# raspi-rfid-rc522.net
KiCad netlist of a schematic drawn in EAGLE
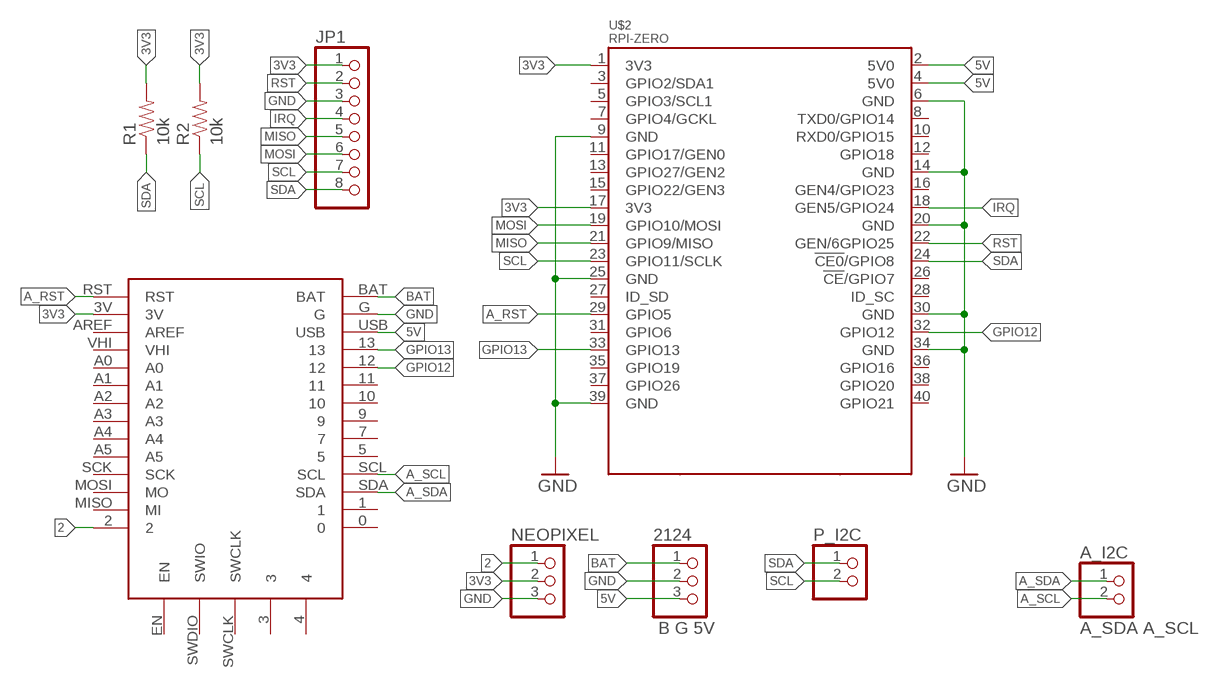
[diagram p0: schematic, sheet 1]

(export (version "E")
  (design (tool "Eeschema 10.0.6"))
  (components
    (comp (ref "2124")
      (value "B G 5V")
      (footprint "eagle-import:1X03")
      (libsource (lib "eagle-import") (part "PINHD-1X3"))
    )
    (comp (ref "A_I2C")
      (value "A_SDA A_SCL")
      (footprint "eagle-import:1X02")
      (libsource (lib "eagle-import") (part "PINHD-1X2"))
    )
    (comp (ref "JP1")
      (value "PINHD-1X8/90")
      (footprint "eagle-import:1X08_90")
      (libsource (lib "eagle-import") (part "PINHD-1X8/90"))
    )
    (comp (ref "NEOPIXEL")
      (value "PINHD-1X3")
      (footprint "eagle-import:1X03")
      (libsource (lib "eagle-import") (part "PINHD-1X3"))
    )
    (comp (ref "P_I2C")
      (value "PINHD-1X2")
      (footprint "eagle-import:1X02")
      (libsource (lib "eagle-import") (part "PINHD-1X2"))
    )
    (comp (ref "R1")
      (value "10k")
      (footprint "eagle-import:0603-RES")
      (libsource (lib "eagle-import") (part "RESISTOR0603-RES"))
    )
    (comp (ref "R2")
      (value "10k")
      (footprint "eagle-import:0603-RES")
      (libsource (lib "eagle-import") (part "RESISTOR0603-RES"))
    )
    (comp (ref "U$1")
      (value "ITSYBITSYM4")
      (footprint "eagle-import:ITSYBITSYM4")
      (libsource (lib "eagle-import") (part "ITSYBITSYM4"))
    )
    (comp (ref "U$2")
      (value "RPI-ZERO")
      (footprint "eagle-import:RASPBERRYPI_BASTELSTUBE_V13_RASPI_BOARD_B+_FULL")
      (libsource (lib "eagle-import") (part "RPI-ZERO"))
    )
  )
  (nets
    (net (code "1") (name "2") (class "Default")
      (node (ref "NEOPIXEL") (pin "1") (pinfunction "1_1") (pintype "passive"))
      (node (ref "U$1") (pin "2") (pinfunction "2_2") (pintype "bidirectional"))
    )
    (net (code "2") (name "3V3") (class "Default")
      (node (ref "JP1") (pin "1") (pinfunction "1_1") (pintype "passive"))
      (node (ref "NEOPIXEL") (pin "2") (pinfunction "2_2") (pintype "passive"))
      (node (ref "R1") (pin "2") (pinfunction "2_2") (pintype "passive"))
      (node (ref "R2") (pin "2") (pinfunction "2_2") (pintype "passive"))
      (node (ref "U$1") (pin "3V") (pinfunction "3V_3V") (pintype "bidirectional"))
      (node (ref "U$2") (pin "1") (pinfunction "3V3_1") (pintype "power_in"))
      (node (ref "U$2") (pin "17") (pinfunction "3V3_17") (pintype "power_in"))
    )
    (net (code "3") (name "5V") (class "Default")
      (node (ref "2124") (pin "3") (pinfunction "3_3") (pintype "passive"))
      (node (ref "U$1") (pin "USB") (pinfunction "USB_USB") (pintype "bidirectional"))
      (node (ref "U$2") (pin "2") (pinfunction "5V0_2") (pintype "power_in"))
      (node (ref "U$2") (pin "4") (pinfunction "5V0_4") (pintype "power_in"))
    )
    (net (code "4") (name "A_RST") (class "Default")
      (node (ref "U$1") (pin "RST") (pinfunction "RST_RST") (pintype "bidirectional"))
      (node (ref "U$2") (pin "29") (pinfunction "GPIO5_29") (pintype "bidirectional"))
    )
    (net (code "5") (name "A_SCL") (class "Default")
      (node (ref "A_I2C") (pin "2") (pinfunction "2_2") (pintype "passive"))
      (node (ref "U$1") (pin "SCL") (pinfunction "SCL_SCL") (pintype "bidirectional"))
    )
    (net (code "6") (name "A_SDA") (class "Default")
      (node (ref "A_I2C") (pin "1") (pinfunction "1_1") (pintype "passive"))
      (node (ref "U$1") (pin "SDA") (pinfunction "SDA_SDA") (pintype "bidirectional"))
    )
    (net (code "7") (name "BAT") (class "Default")
      (node (ref "2124") (pin "1") (pinfunction "1_1") (pintype "passive"))
      (node (ref "U$1") (pin "BAT") (pinfunction "BAT_BAT") (pintype "bidirectional"))
    )
    (net (code "8") (name "GND") (class "Default")
      (node (ref "2124") (pin "2") (pinfunction "2_2") (pintype "passive"))
      (node (ref "JP1") (pin "3") (pinfunction "3_3") (pintype "passive"))
      (node (ref "NEOPIXEL") (pin "3") (pinfunction "3_3") (pintype "passive"))
      (node (ref "U$1") (pin "G") (pinfunction "G_G") (pintype "bidirectional"))
      (node (ref "U$2") (pin "14") (pinfunction "GND_14") (pintype "power_in"))
      (node (ref "U$2") (pin "20") (pinfunction "GND_20") (pintype "power_in"))
      (node (ref "U$2") (pin "25") (pinfunction "GND_25") (pintype "power_in"))
      (node (ref "U$2") (pin "30") (pinfunction "GND_30") (pintype "power_in"))
      (node (ref "U$2") (pin "34") (pinfunction "GND_34") (pintype "power_in"))
      (node (ref "U$2") (pin "39") (pinfunction "GND_39") (pintype "power_in"))
      (node (ref "U$2") (pin "6") (pinfunction "GND_6") (pintype "power_in"))
      (node (ref "U$2") (pin "9") (pinfunction "GND_9") (pintype "power_in"))
    )
    (net (code "9") (name "GPIO12") (class "Default")
      (node (ref "U$1") (pin "12") (pinfunction "12_12") (pintype "bidirectional"))
      (node (ref "U$2") (pin "32") (pinfunction "GPIO12_32") (pintype "bidirectional"))
    )
    (net (code "10") (name "GPIO13") (class "Default")
      (node (ref "U$1") (pin "13") (pinfunction "13_13") (pintype "bidirectional"))
      (node (ref "U$2") (pin "33") (pinfunction "GPIO13_33") (pintype "bidirectional"))
    )
    (net (code "11") (name "IRQ") (class "Default")
      (node (ref "JP1") (pin "4") (pinfunction "4_4") (pintype "passive"))
      (node (ref "U$2") (pin "18") (pinfunction "GEN5/GPIO24_18") (pintype "bidirectional"))
    )
    (net (code "12") (name "MISO") (class "Default")
      (node (ref "JP1") (pin "5") (pinfunction "5_5") (pintype "passive"))
      (node (ref "U$2") (pin "21") (pinfunction "GPIO9/MISO_21") (pintype "bidirectional"))
    )
    (net (code "13") (name "MOSI") (class "Default")
      (node (ref "JP1") (pin "6") (pinfunction "6_6") (pintype "passive"))
      (node (ref "U$2") (pin "19") (pinfunction "GPIO10/MOSI_19") (pintype "bidirectional"))
    )
    (net (code "14") (name "RST") (class "Default")
      (node (ref "JP1") (pin "2") (pinfunction "2_2") (pintype "passive"))
      (node (ref "U$2") (pin "22") (pinfunction "GEN/6GPIO25_22") (pintype "bidirectional"))
    )
    (net (code "15") (name "SCL") (class "Default")
      (node (ref "JP1") (pin "7") (pinfunction "7_7") (pintype "passive"))
      (node (ref "P_I2C") (pin "2") (pinfunction "2_2") (pintype "passive"))
      (node (ref "R2") (pin "1") (pinfunction "1_1") (pintype "passive"))
      (node (ref "U$2") (pin "23") (pinfunction "GPIO11/SCLK_23") (pintype "bidirectional"))
    )
    (net (code "16") (name "SDA") (class "Default")
      (node (ref "JP1") (pin "8") (pinfunction "8_8") (pintype "passive"))
      (node (ref "P_I2C") (pin "1") (pinfunction "1_1") (pintype "passive"))
      (node (ref "R1") (pin "1") (pinfunction "1_1") (pintype "passive"))
      (node (ref "U$2") (pin "24") (pinfunction "~{CE0}/GPIO8_24") (pintype "bidirectional"))
    )
    (net (code "17") (name "unconnected-(U$1-MI-PadMISO)") (class "Default")
      (node (ref "U$1") (pin "MISO") (pinfunction "MI_MISO") (pintype "bidirectional"))
    )
    (net (code "18") (name "unconnected-(U$1-MO-PadMOSI)") (class "Default")
      (node (ref "U$1") (pin "MOSI") (pinfunction "MO_MOSI") (pintype "bidirectional"))
    )
    (net (code "19") (name "unconnected-(U$1-Pad0)") (class "Default")
      (node (ref "U$1") (pin "0") (pinfunction "0_0") (pintype "bidirectional"))
    )
    (net (code "20") (name "unconnected-(U$1-Pad1)") (class "Default")
      (node (ref "U$1") (pin "1") (pinfunction "1_1") (pintype "bidirectional"))
    )
    (net (code "21") (name "unconnected-(U$1-Pad3)") (class "Default")
      (node (ref "U$1") (pin "3") (pinfunction "3_3") (pintype "bidirectional"))
    )
    (net (code "22") (name "unconnected-(U$1-Pad4)") (class "Default")
      (node (ref "U$1") (pin "4") (pinfunction "4_4") (pintype "bidirectional"))
    )
    (net (code "23") (name "unconnected-(U$1-Pad5)") (class "Default")
      (node (ref "U$1") (pin "5") (pinfunction "5_5") (pintype "bidirectional"))
    )
    (net (code "24") (name "unconnected-(U$1-Pad7)") (class "Default")
      (node (ref "U$1") (pin "7") (pinfunction "7_7") (pintype "bidirectional"))
    )
    (net (code "25") (name "unconnected-(U$1-Pad9)") (class "Default")
      (node (ref "U$1") (pin "9") (pinfunction "9_9") (pintype "bidirectional"))
    )
    (net (code "26") (name "unconnected-(U$1-Pad10)") (class "Default")
      (node (ref "U$1") (pin "10") (pinfunction "10_10") (pintype "bidirectional"))
    )
    (net (code "27") (name "unconnected-(U$1-Pad11)") (class "Default")
      (node (ref "U$1") (pin "11") (pinfunction "11_11") (pintype "bidirectional"))
    )
    (net (code "28") (name "unconnected-(U$1-PadA0)") (class "Default")
      (node (ref "U$1") (pin "A0") (pinfunction "A0_A0") (pintype "bidirectional"))
    )
    (net (code "29") (name "unconnected-(U$1-PadA1)") (class "Default")
      (node (ref "U$1") (pin "A1") (pinfunction "A1_A1") (pintype "bidirectional"))
    )
    (net (code "30") (name "unconnected-(U$1-PadA2)") (class "Default")
      (node (ref "U$1") (pin "A2") (pinfunction "A2_A2") (pintype "bidirectional"))
    )
    (net (code "31") (name "unconnected-(U$1-PadA3)") (class "Default")
      (node (ref "U$1") (pin "A3") (pinfunction "A3_A3") (pintype "bidirectional"))
    )
    (net (code "32") (name "unconnected-(U$1-PadA4)") (class "Default")
      (node (ref "U$1") (pin "A4") (pinfunction "A4_A4") (pintype "bidirectional"))
    )
    (net (code "33") (name "unconnected-(U$1-PadA5)") (class "Default")
      (node (ref "U$1") (pin "A5") (pinfunction "A5_A5") (pintype "bidirectional"))
    )
    (net (code "34") (name "unconnected-(U$1-PadAREF)") (class "Default")
      (node (ref "U$1") (pin "AREF") (pinfunction "AREF_AREF") (pintype "bidirectional"))
    )
    (net (code "35") (name "unconnected-(U$1-PadEN)") (class "Default")
      (node (ref "U$1") (pin "EN") (pinfunction "EN_EN") (pintype "bidirectional"))
    )
    (net (code "36") (name "unconnected-(U$1-PadSCK)") (class "Default")
      (node (ref "U$1") (pin "SCK") (pinfunction "SCK_SCK") (pintype "bidirectional"))
    )
    (net (code "37") (name "unconnected-(U$1-PadSWCLK)") (class "Default")
      (node (ref "U$1") (pin "SWCLK") (pinfunction "SWCLK_SWCLK") (pintype "bidirectional"))
    )
    (net (code "38") (name "unconnected-(U$1-PadVHI)") (class "Default")
      (node (ref "U$1") (pin "VHI") (pinfunction "VHI_VHI") (pintype "bidirectional"))
    )
    (net (code "39") (name "unconnected-(U$1-SWIO-PadSWDIO)") (class "Default")
      (node (ref "U$1") (pin "SWDIO") (pinfunction "SWIO_SWDIO") (pintype "bidirectional"))
    )
    (net (code "40") (name "unconnected-(U$2-GEN4{slash}GPIO23-Pad16)") (class "Default")
      (node (ref "U$2") (pin "16") (pinfunction "GEN4/GPIO23_16") (pintype "bidirectional"))
    )
    (net (code "41") (name "unconnected-(U$2-GPIO2{slash}SDA1-Pad3)") (class "Default")
      (node (ref "U$2") (pin "3") (pinfunction "GPIO2/SDA1_3") (pintype "bidirectional"))
    )
    (net (code "42") (name "unconnected-(U$2-GPIO3{slash}SCL1-Pad5)") (class "Default")
      (node (ref "U$2") (pin "5") (pinfunction "GPIO3/SCL1_5") (pintype "bidirectional"))
    )
    (net (code "43") (name "unconnected-(U$2-GPIO4{slash}GCKL-Pad7)") (class "Default")
      (node (ref "U$2") (pin "7") (pinfunction "GPIO4/GCKL_7") (pintype "bidirectional"))
    )
    (net (code "44") (name "unconnected-(U$2-GPIO6-Pad31)") (class "Default")
      (node (ref "U$2") (pin "31") (pinfunction "GPIO6_31") (pintype "bidirectional"))
    )
    (net (code "45") (name "unconnected-(U$2-GPIO16-Pad36)") (class "Default")
      (node (ref "U$2") (pin "36") (pinfunction "GPIO16_36") (pintype "bidirectional"))
    )
    (net (code "46") (name "unconnected-(U$2-GPIO17{slash}GEN0-Pad11)") (class "Default")
      (node (ref "U$2") (pin "11") (pinfunction "GPIO17/GEN0_11") (pintype "bidirectional"))
    )
    (net (code "47") (name "unconnected-(U$2-GPIO18-Pad12)") (class "Default")
      (node (ref "U$2") (pin "12") (pinfunction "GPIO18_12") (pintype "bidirectional"))
    )
    (net (code "48") (name "unconnected-(U$2-GPIO19-Pad35)") (class "Default")
      (node (ref "U$2") (pin "35") (pinfunction "GPIO19_35") (pintype "bidirectional"))
    )
    (net (code "49") (name "unconnected-(U$2-GPIO20-Pad38)") (class "Default")
      (node (ref "U$2") (pin "38") (pinfunction "GPIO20_38") (pintype "bidirectional"))
    )
    (net (code "50") (name "unconnected-(U$2-GPIO21-Pad40)") (class "Default")
      (node (ref "U$2") (pin "40") (pinfunction "GPIO21_40") (pintype "bidirectional"))
    )
    (net (code "51") (name "unconnected-(U$2-GPIO22{slash}GEN3-Pad15)") (class "Default")
      (node (ref "U$2") (pin "15") (pinfunction "GPIO22/GEN3_15") (pintype "bidirectional"))
    )
    (net (code "52") (name "unconnected-(U$2-GPIO26-Pad37)") (class "Default")
      (node (ref "U$2") (pin "37") (pinfunction "GPIO26_37") (pintype "bidirectional"))
    )
    (net (code "53") (name "unconnected-(U$2-GPIO27{slash}GEN2-Pad13)") (class "Default")
      (node (ref "U$2") (pin "13") (pinfunction "GPIO27/GEN2_13") (pintype "bidirectional"))
    )
    (net (code "54") (name "unconnected-(U$2-ID_SC-Pad28)") (class "Default")
      (node (ref "U$2") (pin "28") (pinfunction "ID_SC_28") (pintype "bidirectional"))
    )
    (net (code "55") (name "unconnected-(U$2-ID_SD-Pad27)") (class "Default")
      (node (ref "U$2") (pin "27") (pinfunction "ID_SD_27") (pintype "bidirectional"))
    )
    (net (code "56") (name "unconnected-(U$2-RXD0{slash}GPIO15-Pad10)") (class "Default")
      (node (ref "U$2") (pin "10") (pinfunction "RXD0/GPIO15_10") (pintype "bidirectional"))
    )
    (net (code "57") (name "unconnected-(U$2-TXD0{slash}GPIO14-Pad8)") (class "Default")
      (node (ref "U$2") (pin "8") (pinfunction "TXD0/GPIO14_8") (pintype "bidirectional"))
    )
    (net (code "58") (name "unconnected-(U$2-~{CE}{slash}GPIO7-Pad26)") (class "Default")
      (node (ref "U$2") (pin "26") (pinfunction "~{CE}/GPIO7_26") (pintype "bidirectional"))
    )
  )
)
